# cociclo_05.net
KiCad netlist of a schematic drawn in EAGLE
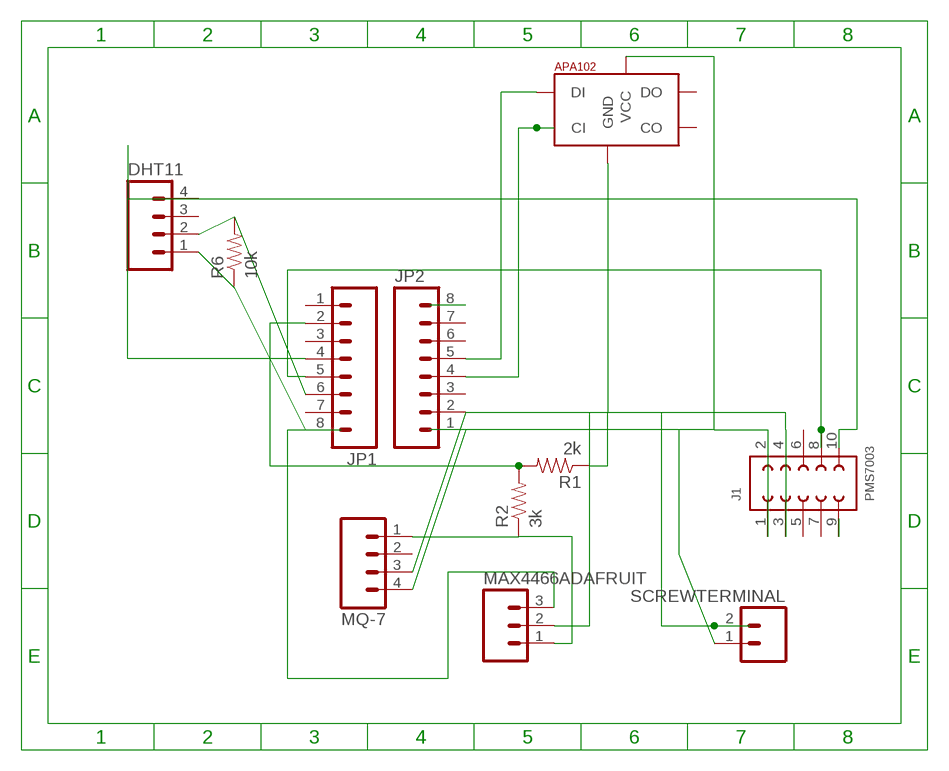
[diagram p0: schematic, sheet 1]

(export (version "E")
  (design (tool "Eeschema 10.0.6"))
  (components
    (comp (ref "DHT11")
      (value "M04PTH")
      (footprint "eagle-import:1X04")
      (libsource (lib "eagle-import") (part "M04PTH"))
    )
    (comp (ref "J1")
      (value "PMS7003")
      (footprint "eagle-import:621X1021021")
      (libsource (lib "eagle-import") (part "621X1021021"))
    )
    (comp (ref "JP1")
      (value "M08")
      (footprint "eagle-import:1X08_ROUND")
      (libsource (lib "eagle-import") (part "M08"))
    )
    (comp (ref "JP2")
      (value "M08")
      (footprint "eagle-import:1X08_ROUND")
      (libsource (lib "eagle-import") (part "M08"))
    )
    (comp (ref "MAX4466ADAFRUIT")
      (value "M03PTH")
      (footprint "eagle-import:1X03")
      (libsource (lib "eagle-import") (part "M03PTH"))
    )
    (comp (ref "MQ-7")
      (value "M04PTH")
      (footprint "eagle-import:1X04")
      (libsource (lib "eagle-import") (part "M04PTH"))
    )
    (comp (ref "R1")
      (value "2k")
      (footprint "eagle-import:1206")
      (libsource (lib "eagle-import") (part "RESISTOR1206"))
    )
    (comp (ref "R2")
      (value "3k")
      (footprint "eagle-import:1206")
      (libsource (lib "eagle-import") (part "RESISTOR1206"))
    )
    (comp (ref "R6")
      (value "10k")
      (footprint "eagle-import:1206")
      (libsource (lib "eagle-import") (part "RESISTOR1206"))
    )
    (comp (ref "SCREWTERMINAL")
      (value "M023.5MM")
      (footprint "eagle-import:SCREWTERMINAL-3.5MM-2")
      (libsource (lib "eagle-import") (part "M023.5MM"))
    )
    (comp (ref "SK9822LED")
      (value "APA1025050")
      (footprint "eagle-import:APA102_5050")
      (libsource (lib "eagle-import") (part "APA1025050"))
    )
  )
  (nets
    (net (code "1") (name "Net-(DHT11-Pad1)") (class "Default")
      (node (ref "DHT11") (pin "1") (pinfunction "1_1") (pintype "passive"))
      (node (ref "JP1") (pin "8") (pinfunction "8_8") (pintype "passive"))
      (node (ref "MAX4466ADAFRUIT") (pin "3") (pinfunction "3_3") (pintype "passive"))
      (node (ref "R6") (pin "1") (pinfunction "1_1") (pintype "passive"))
    )
    (net (code "2") (name "Net-(DHT11-Pad2)") (class "Default")
      (node (ref "DHT11") (pin "2") (pinfunction "2_2") (pintype "passive"))
      (node (ref "JP1") (pin "6") (pinfunction "6_6") (pintype "passive"))
      (node (ref "R6") (pin "2") (pinfunction "2_2") (pintype "passive"))
    )
    (net (code "3") (name "Net-(J1-2)") (class "Default")
      (node (ref "DHT11") (pin "4") (pinfunction "4_4") (pintype "passive"))
      (node (ref "J1") (pin "3") (pinfunction "2_3") (pintype "passive"))
      (node (ref "J1") (pin "4") (pinfunction "9_4") (pintype "passive"))
      (node (ref "JP2") (pin "2") (pinfunction "2_2") (pintype "passive"))
      (node (ref "MAX4466ADAFRUIT") (pin "2") (pinfunction "2_2") (pintype "passive"))
      (node (ref "MQ-7") (pin "3") (pinfunction "3_3") (pintype "passive"))
      (node (ref "R1") (pin "1") (pinfunction "1_1") (pintype "passive"))
      (node (ref "SCREWTERMINAL") (pin "2") (pinfunction "2_2") (pintype "passive"))
      (node (ref "SK9822LED") (pin "6") (pinfunction "GND_6") (pintype "bidirectional"))
    )
    (net (code "4") (name "Net-(J1-6)") (class "Default")
      (node (ref "J1") (pin "10") (pinfunction "6_10") (pintype "passive"))
      (node (ref "JP1") (pin "4") (pinfunction "4_4") (pintype "passive"))
    )
    (net (code "5") (name "Net-(J1-7)") (class "Default")
      (node (ref "J1") (pin "8") (pinfunction "7_8") (pintype "passive"))
      (node (ref "JP1") (pin "5") (pinfunction "5_5") (pintype "passive"))
    )
    (net (code "6") (name "Net-(J1-10)") (class "Default")
      (node (ref "J1") (pin "1") (pinfunction "1_1") (pintype "passive"))
      (node (ref "J1") (pin "2") (pinfunction "10_2") (pintype "passive"))
      (node (ref "JP2") (pin "1") (pinfunction "1_1") (pintype "passive"))
      (node (ref "MQ-7") (pin "4") (pinfunction "4_4") (pintype "passive"))
      (node (ref "SCREWTERMINAL") (pin "1") (pinfunction "1_1") (pintype "passive"))
      (node (ref "SK9822LED") (pin "1") (pinfunction "VCC_1") (pintype "bidirectional"))
    )
    (net (code "7") (name "Net-(JP1-Pad2)") (class "Default")
      (node (ref "JP1") (pin "2") (pinfunction "2_2") (pintype "passive"))
      (node (ref "R1") (pin "2") (pinfunction "2_2") (pintype "passive"))
      (node (ref "R2") (pin "2") (pinfunction "2_2") (pintype "passive"))
    )
    (net (code "8") (name "Net-(MAX4466ADAFRUIT-Pad1)") (class "Default")
      (node (ref "MAX4466ADAFRUIT") (pin "1") (pinfunction "1_1") (pintype "passive"))
      (node (ref "MQ-7") (pin "1") (pinfunction "1_1") (pintype "passive"))
      (node (ref "R2") (pin "1") (pinfunction "1_1") (pintype "passive"))
    )
    (net (code "9") (name "Net-(SK9822LED-CI)") (class "Default")
      (node (ref "JP2") (pin "4") (pinfunction "4_4") (pintype "passive"))
      (node (ref "SK9822LED") (pin "5") (pinfunction "CI_5") (pintype "bidirectional"))
    )
    (net (code "10") (name "Net-(SK9822LED-DI)") (class "Default")
      (node (ref "JP2") (pin "5") (pinfunction "5_5") (pintype "passive"))
      (node (ref "SK9822LED") (pin "4") (pinfunction "DI_4") (pintype "bidirectional"))
    )
    (net (code "11") (name "unconnected-(DHT11-Pad3)") (class "Default")
      (node (ref "DHT11") (pin "3") (pinfunction "3_3") (pintype "passive"))
    )
    (net (code "12") (name "unconnected-(J1-3-Pad5)") (class "Default")
      (node (ref "J1") (pin "5") (pinfunction "3_5") (pintype "passive"))
    )
    (net (code "13") (name "unconnected-(J1-4-Pad7)") (class "Default")
      (node (ref "J1") (pin "7") (pinfunction "4_7") (pintype "passive"))
    )
    (net (code "14") (name "unconnected-(J1-5-Pad9)") (class "Default")
      (node (ref "J1") (pin "9") (pinfunction "5_9") (pintype "passive"))
    )
    (net (code "15") (name "unconnected-(J1-8-Pad6)") (class "Default")
      (node (ref "J1") (pin "6") (pinfunction "8_6") (pintype "passive"))
    )
    (net (code "16") (name "unconnected-(JP1-Pad1)") (class "Default")
      (node (ref "JP1") (pin "1") (pinfunction "1_1") (pintype "passive"))
    )
    (net (code "17") (name "unconnected-(JP1-Pad3)") (class "Default")
      (node (ref "JP1") (pin "3") (pinfunction "3_3") (pintype "passive"))
    )
    (net (code "18") (name "unconnected-(JP1-Pad7)") (class "Default")
      (node (ref "JP1") (pin "7") (pinfunction "7_7") (pintype "passive"))
    )
    (net (code "19") (name "unconnected-(JP2-Pad3)") (class "Default")
      (node (ref "JP2") (pin "3") (pinfunction "3_3") (pintype "passive"))
    )
    (net (code "20") (name "unconnected-(JP2-Pad6)") (class "Default")
      (node (ref "JP2") (pin "6") (pinfunction "6_6") (pintype "passive"))
    )
    (net (code "21") (name "unconnected-(JP2-Pad7)") (class "Default")
      (node (ref "JP2") (pin "7") (pinfunction "7_7") (pintype "passive"))
    )
    (net (code "22") (name "unconnected-(JP2-Pad8)") (class "Default")
      (node (ref "JP2") (pin "8") (pinfunction "8_8") (pintype "passive"))
    )
    (net (code "23") (name "unconnected-(MQ-7-Pad2)") (class "Default")
      (node (ref "MQ-7") (pin "2") (pinfunction "2_2") (pintype "passive"))
    )
    (net (code "24") (name "unconnected-(SK9822LED-CO-Pad2)") (class "Default")
      (node (ref "SK9822LED") (pin "2") (pinfunction "CO_2") (pintype "bidirectional"))
    )
    (net (code "25") (name "unconnected-(SK9822LED-DO-Pad3)") (class "Default")
      (node (ref "SK9822LED") (pin "3") (pinfunction "DO_3") (pintype "bidirectional"))
    )
  )
)
